# ANTI-FALL-IR-SENSORs.net
KiCad netlist of a schematic drawn in Altium Designer
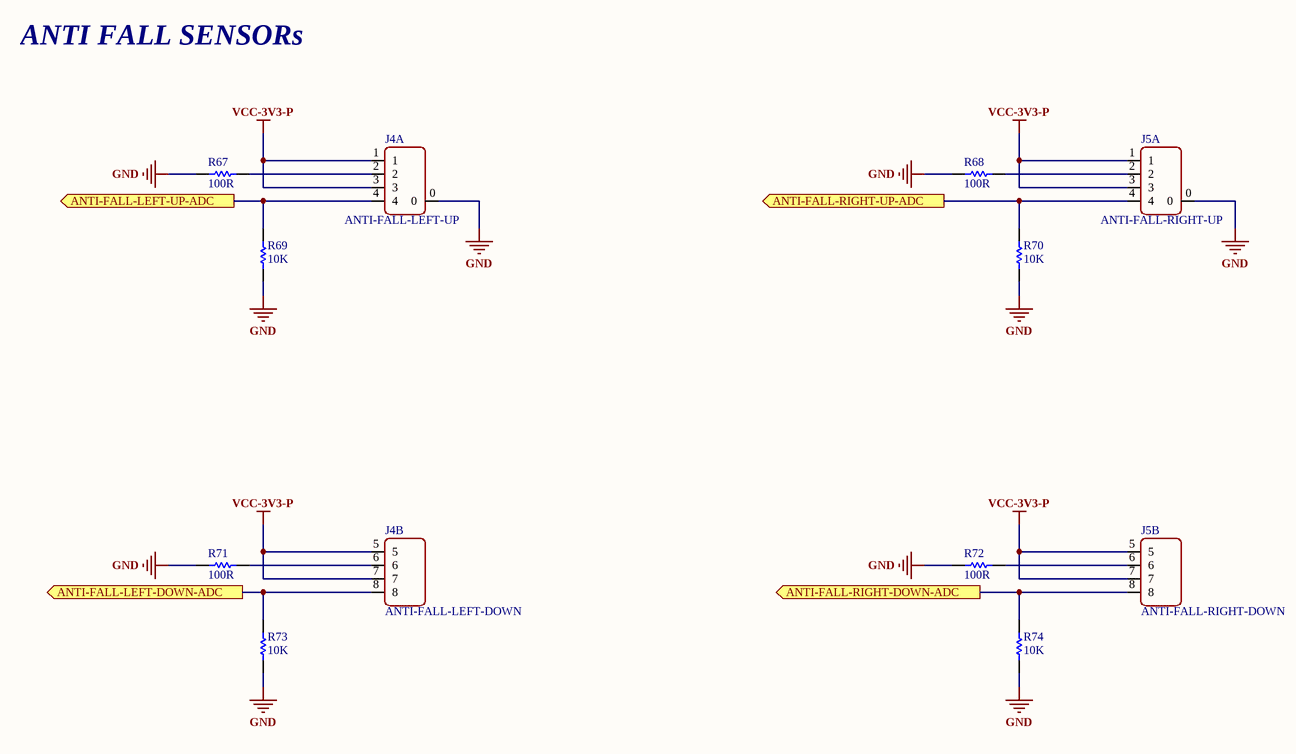
[diagram p0: ANTI-FALL-IR-SENSORs.SchDoc]

(export (version "E")
  (design (tool "Eeschema 10.0.6"))
  (components
    (comp (ref "J4")
      (value "ANTI-FALL-LEFT-UP")
      (footprint "CONN-SMD_8P-P1.50_ZX-ZH1.5-8PWT")
      (description "ZX-ZH1.5-8PWT")
      (libsource (lib "DesignLibrary") (part "HDRx8-2"))
    )
    (comp (ref "J5")
      (value "ANTI-FALL-RIGHT-UP")
      (footprint "CONN-SMD_8P-P1.50_ZX-ZH1.5-8PWT")
      (description "ZX-ZH1.5-8PWT")
      (libsource (lib "DesignLibrary") (part "HDRx8-2"))
    )
    (comp (ref "R67")
      (value "100R")
      (footprint "RES-0402")
      (libsource (lib "DesignLibrary") (part "Resistor-1"))
    )
    (comp (ref "R68")
      (value "100R")
      (footprint "RES-0402")
      (libsource (lib "DesignLibrary") (part "Resistor-1"))
    )
    (comp (ref "R69")
      (value "10K")
      (footprint "RES-0402")
      (libsource (lib "DesignLibrary") (part "Resistor-1"))
    )
    (comp (ref "R70")
      (value "10K")
      (footprint "RES-0402")
      (libsource (lib "DesignLibrary") (part "Resistor-1"))
    )
    (comp (ref "R71")
      (value "100R")
      (footprint "RES-0402")
      (libsource (lib "DesignLibrary") (part "Resistor-1"))
    )
    (comp (ref "R72")
      (value "100R")
      (footprint "RES-0402")
      (libsource (lib "DesignLibrary") (part "Resistor-1"))
    )
    (comp (ref "R73")
      (value "10K")
      (footprint "RES-0402")
      (libsource (lib "DesignLibrary") (part "Resistor-1"))
    )
    (comp (ref "R74")
      (value "10K")
      (footprint "RES-0402")
      (libsource (lib "DesignLibrary") (part "Resistor-1"))
    )
  )
  (nets
    (net (code "1") (name "/ANTI-FALL-LEFT-DOWN-ADC") (class "Default")
      (node (ref "J4") (pin "8") (pinfunction "8_8") (pintype "passive"))
      (node (ref "R73") (pin "2") (pintype "passive"))
    )
    (net (code "2") (name "/ANTI-FALL-LEFT-UP-ADC") (class "Default")
      (node (ref "J4") (pin "4") (pinfunction "4_4") (pintype "passive"))
      (node (ref "R69") (pin "2") (pintype "passive"))
    )
    (net (code "3") (name "/ANTI-FALL-RIGHT-DOWN-ADC") (class "Default")
      (node (ref "J5") (pin "8") (pinfunction "8_8") (pintype "passive"))
      (node (ref "R74") (pin "2") (pintype "passive"))
    )
    (net (code "4") (name "/ANTI-FALL-RIGHT-UP-ADC") (class "Default")
      (node (ref "J5") (pin "4") (pinfunction "4_4") (pintype "passive"))
      (node (ref "R70") (pin "2") (pintype "passive"))
    )
    (net (code "5") (name "GND") (class "Default")
      (node (ref "J4") (pin "0") (pinfunction "0_0") (pintype "passive"))
      (node (ref "J5") (pin "0") (pinfunction "0_0") (pintype "passive"))
      (node (ref "R67") (pin "1") (pintype "passive"))
      (node (ref "R68") (pin "1") (pintype "passive"))
      (node (ref "R69") (pin "1") (pintype "passive"))
      (node (ref "R70") (pin "1") (pintype "passive"))
      (node (ref "R71") (pin "1") (pintype "passive"))
      (node (ref "R72") (pin "1") (pintype "passive"))
      (node (ref "R73") (pin "1") (pintype "passive"))
      (node (ref "R74") (pin "1") (pintype "passive"))
    )
    (net (code "6") (name "Net-(J4-Pad2)") (class "Default")
      (node (ref "J4") (pin "2") (pinfunction "2_2") (pintype "passive"))
      (node (ref "R67") (pin "2") (pintype "passive"))
    )
    (net (code "7") (name "Net-(J4-Pad6)") (class "Default")
      (node (ref "J4") (pin "6") (pinfunction "6_6") (pintype "passive"))
      (node (ref "R71") (pin "2") (pintype "passive"))
    )
    (net (code "8") (name "Net-(J5-Pad2)") (class "Default")
      (node (ref "J5") (pin "2") (pinfunction "2_2") (pintype "passive"))
      (node (ref "R68") (pin "2") (pintype "passive"))
    )
    (net (code "9") (name "Net-(J5-Pad6)") (class "Default")
      (node (ref "J5") (pin "6") (pinfunction "6_6") (pintype "passive"))
      (node (ref "R72") (pin "2") (pintype "passive"))
    )
    (net (code "10") (name "VCC-3V3-P") (class "Default")
      (node (ref "J4") (pin "1") (pinfunction "1_1") (pintype "passive"))
      (node (ref "J4") (pin "3") (pinfunction "3_3") (pintype "passive"))
      (node (ref "J4") (pin "5") (pinfunction "5_5") (pintype "passive"))
      (node (ref "J4") (pin "7") (pinfunction "7_7") (pintype "passive"))
      (node (ref "J5") (pin "1") (pinfunction "1_1") (pintype "passive"))
      (node (ref "J5") (pin "3") (pinfunction "3_3") (pintype "passive"))
      (node (ref "J5") (pin "5") (pinfunction "5_5") (pintype "passive"))
      (node (ref "J5") (pin "7") (pinfunction "7_7") (pintype "passive"))
    )
  )
)
